# 5v_power.net
KiCad netlist of a schematic drawn in Altium Designer
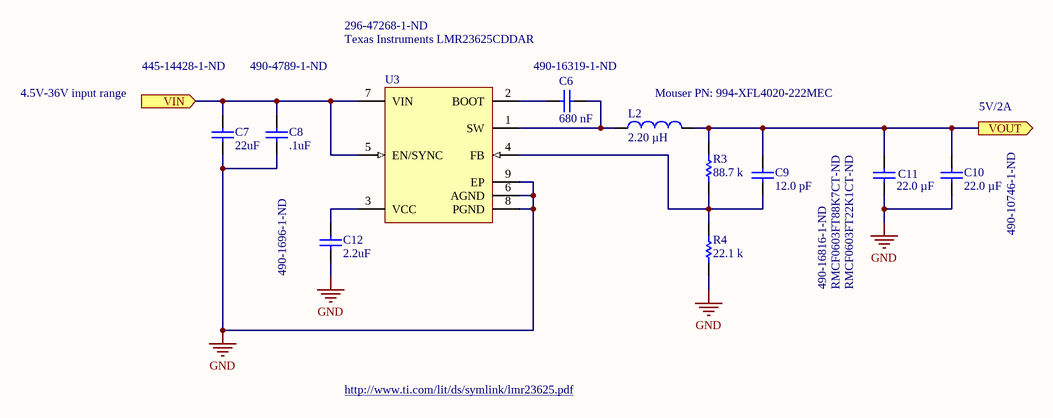
[diagram p0: 5v_power.SchDoc]

(export (version "E")
  (design (tool "Eeschema 10.0.6"))
  (components
    (comp (ref "C6")
      (value "Murata GRM21BR71H684KAC4L")
      (footprint "PCB-xrh88671zmf2jss4mnlt-1")
      (description "Cap Ceramic 0.68uF 50V X7R 10% Pad SMD 0805 125C T/R")
      (fields
        (field (name "MANUFACTURER PART NUMBER") "GRM21BR71H684KAC4L")
        (field (name "CAPACITANCE") "680 nF")
      )
      (libsource (lib "CommunityVault") (part "CMP-44008e6100d59bc7-1"))
    )
    (comp (ref "C7")
      (value "Cap")
      (footprint "PCB-lllx3wppxbec679u3f24-1")
      (description "C Series 0805 22 uF 35 V ±20 % Tolerance X5R SMT Multilayer Ceramic Capacitor")
      (fields
        (field (name "MANUFACTURER PART NUMBER") "C2012X5R1V226M125AC")
        (field (name "CAPACITANCE") "22uF")
      )
      (libsource (lib "CommunityVault") (part "CMP-0d44c5e3fbabd283-1"))
    )
    (comp (ref "C8")
      (value "Murata GCM21BR72A104KA37L")
      (footprint "CAPC2013X140X45ML15T25")
      (description "CAP CER 0.1UF 100V 10% X7R 0805")
      (fields (field (name "CAPACITANCE") ".1uF"))
      (libsource (lib "CommunityVault") (part "CMP-120358-2"))
    )
    (comp (ref "C9")
      (value "Murata GRM21A5C2D120JW01D")
      (footprint "PCB-xrh88671zmf2jss4mnlt-1")
      (description "Cap Ceramic 12pF 200V C0G 5% SMD 0805 125°C Paper T/R")
      (fields
        (field (name "MANUFACTURER PART NUMBER") "GRM21A5C2D120JW01D")
        (field (name "CAPACITANCE") "12.0 pF")
      )
      (libsource (lib "CommunityVault") (part "CMP-50dd9b1f09f28f1a-1"))
    )
    (comp (ref "C10")
      (value "Murata GRM21BR61A226ME44L")
      (footprint "PCB-xrh88671zmf2jss4mnlt-1")
      (description "0805 22 uF 10 V ±20% Tolerance X5R Multilayer Ceramic Chip Capacitor")
      (fields
        (field (name "MANUFACTURER PART NUMBER") "GRM21BR61A226ME44L")
        (field (name "CAPACITANCE") "22.0 µF")
      )
      (libsource (lib "CommunityVault") (part "CMP-7d69b6ab24aca2ae-1"))
    )
    (comp (ref "C11")
      (value "Murata GRM21BR61A226ME44L")
      (footprint "PCB-xrh88671zmf2jss4mnlt-1")
      (description "0805 22 uF 10 V ±20% Tolerance X5R Multilayer Ceramic Chip Capacitor")
      (fields
        (field (name "MANUFACTURER PART NUMBER") "GRM21BR61A226ME44L")
        (field (name "CAPACITANCE") "22.0 µF")
      )
      (libsource (lib "CommunityVault") (part "CMP-7d69b6ab24aca2ae-1"))
    )
    (comp (ref "C12")
      (value "Murata GRM21BR71A225KA01L")
      (footprint "CAPC2013X135X50LL10T20")
      (description "CAP CER 2.2UF 10V 10% X7R 0805")
      (fields (field (name "CAPACITANCE") "2.2uF"))
      (libsource (lib "CommunityVault") (part "CMP-19299739-2"))
    )
    (comp (ref "L2")
      (value "Coilcraft XFL4020-222MEC")
      (footprint "PCB-9d9k809zadibtjsjgh1m-1")
      (description "Power inductor, shielded, 20% tol, SMT, RoHS, halogen free")
      (fields
        (field (name "MANUFACTURER PART NUMBER") "XFL4020-222MEC")
        (field (name "INDUCTANCE") "2.20 µH")
      )
      (libsource (lib "CommunityVault") (part "CMP-3796fe24315fe851-1"))
    )
    (comp (ref "R3")
      (value "Stackpole Electronics RMCF0603FT88K7")
      (footprint "PCB-9ahxsq8gddjqcnfjmojj-1")
      (description "RMCF Series 0603 0.1 W 88.7 kOhm ±1 % ±100 ppm/°C SMT Thick Film Chip Resistor")
      (fields (field (name "MANUFACTURER PART NUMBER") "RMCF0603FT88K7") (field (name "RESISTANCE") "88.7 k"))
      (libsource (lib "CommunityVault") (part "CMP-fc30341ff50423f7-1"))
    )
    (comp (ref "R4")
      (value "Stackpole Electronics RMCF0603FT22K1")
      (footprint "PCB-9ahxsq8gddjqcnfjmojj-1")
      (description "RMCF Series 0603 0.1 W 22.1 kOhm ±1 % ±100 ppm/°C SMT Thick Film Chip Resistor")
      (fields (field (name "MANUFACTURER PART NUMBER") "RMCF0603FT22K1") (field (name "RESISTANCE") "22.1 k"))
      (libsource (lib "CommunityVault") (part "CMP-f875305af60927b2-1"))
    )
    (comp (ref "U3")
      (value "Texas Instruments LMR23625CDDAR")
      (footprint "PCB-d70mjtd98i3vq9jo7u2s-1")
      (description "SIMPLE SWITCHER?, 36V 2.5A Synchronous Step-Down Converter 8-SO PowerPAD -40 to 125")
      (fields (field (name "MANUFACTURER PART NUMBER") "LMR23625CDDAR"))
      (libsource (lib "CommunityVault") (part "SYM-9dcb50cfc7eb420c-1"))
    )
  )
  (nets
    (net (code "1") (name "/VIN") (class "Default")
      (node (ref "C7") (pin "1") (pinfunction "1_1") (pintype "passive"))
      (node (ref "C8") (pin "1") (pinfunction "1_1") (pintype "passive"))
      (node (ref "U3") (pin "5") (pinfunction "EN/SYNC_5") (pintype "input"))
      (node (ref "U3") (pin "7") (pinfunction "VIN_7") (pintype "power_in"))
    )
    (net (code "2") (name "/VOUT") (class "Default")
      (node (ref "C10") (pin "2") (pinfunction "2_2") (pintype "passive"))
      (node (ref "C11") (pin "2") (pinfunction "2_2") (pintype "passive"))
      (node (ref "C9") (pin "2") (pinfunction "2_2") (pintype "passive"))
      (node (ref "L2") (pin "2") (pinfunction "2_2") (pintype "passive"))
      (node (ref "R3") (pin "1") (pinfunction "1_1") (pintype "passive"))
    )
    (net (code "3") (name "GND") (class "Default")
      (node (ref "C10") (pin "1") (pinfunction "1_1") (pintype "passive"))
      (node (ref "C11") (pin "1") (pinfunction "1_1") (pintype "passive"))
      (node (ref "C12") (pin "1") (pinfunction "1_1") (pintype "passive"))
      (node (ref "C7") (pin "2") (pinfunction "2_2") (pintype "passive"))
      (node (ref "C8") (pin "2") (pinfunction "2_2") (pintype "passive"))
      (node (ref "R4") (pin "1") (pinfunction "1_1") (pintype "passive"))
      (node (ref "U3") (pin "6") (pinfunction "AGND_6") (pintype "power_in"))
      (node (ref "U3") (pin "8") (pinfunction "PGND_8") (pintype "power_in"))
      (node (ref "U3") (pin "9") (pinfunction "EP_9") (pintype "power_in"))
    )
    (net (code "4") (name "Net-(U3-BOOT)") (class "Default")
      (node (ref "C6") (pin "2") (pinfunction "2_2") (pintype "passive"))
      (node (ref "U3") (pin "2") (pinfunction "BOOT_2") (pintype "passive"))
    )
    (net (code "5") (name "Net-(U3-FB)") (class "Default")
      (node (ref "C9") (pin "1") (pinfunction "1_1") (pintype "passive"))
      (node (ref "R3") (pin "2") (pinfunction "2_2") (pintype "passive"))
      (node (ref "R4") (pin "2") (pinfunction "2_2") (pintype "passive"))
      (node (ref "U3") (pin "4") (pinfunction "FB_4") (pintype "input"))
    )
    (net (code "6") (name "Net-(U3-SW)") (class "Default")
      (node (ref "C6") (pin "1") (pinfunction "1_1") (pintype "passive"))
      (node (ref "L2") (pin "1") (pinfunction "1_1") (pintype "passive"))
      (node (ref "U3") (pin "1") (pinfunction "SW_1") (pintype "power_in"))
    )
    (net (code "7") (name "Net-(U3-VCC)") (class "Default")
      (node (ref "C12") (pin "2") (pinfunction "2_2") (pintype "passive"))
      (node (ref "U3") (pin "3") (pinfunction "VCC_3") (pintype "power_in"))
    )
  )
)
